# PX4FLOW2_0_CAM_X0.net
KiCad netlist of a schematic drawn in Altium Designer
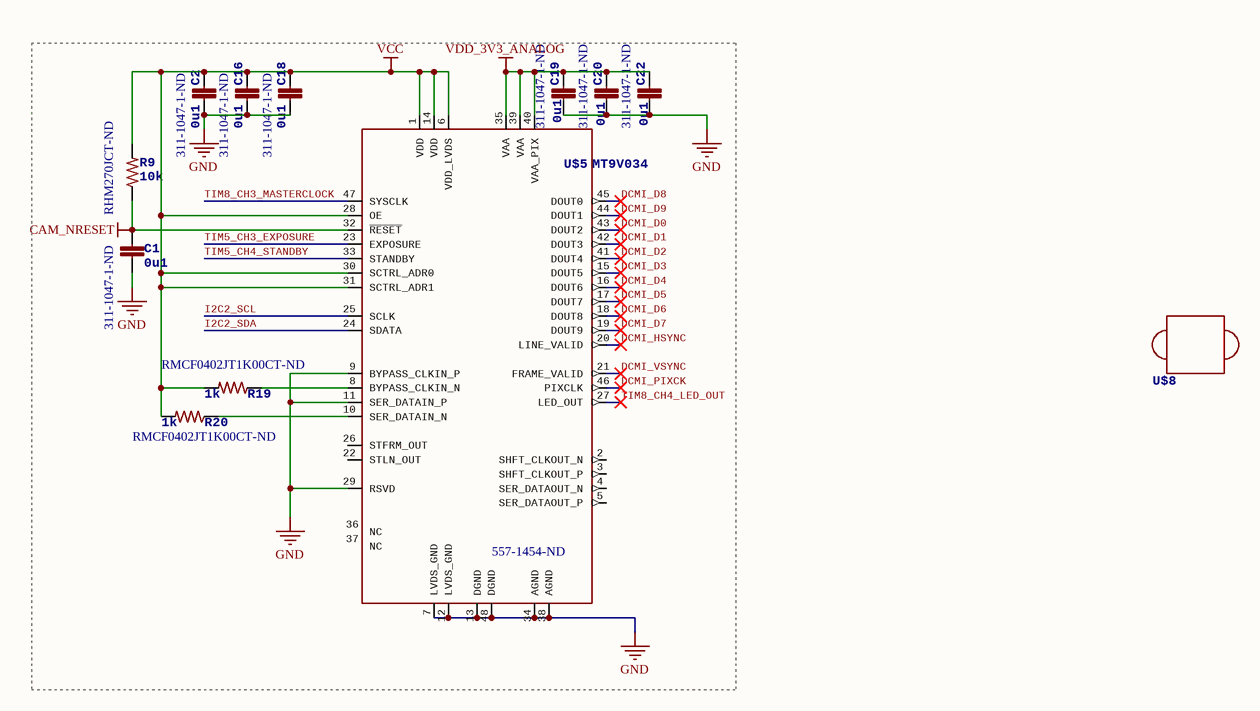
[diagram p0: PX4FLOW2.0_CAM_X0.SchDoc]

(export (version "E")
  (design (tool "Eeschema 10.0.6"))
  (components
    (comp (ref "C1")
      (value "0u1")
      (footprint "0402-CAP")
      (description "CapacitorStandard 0603 ceramic capacitor, and 0.1\" leaded capacitor.")
      (fields
        (field (name "PARTNO") "CC0402ZRY5V7BB104")
        (field (name "SUPPLIER PART NUMBER 1") "311-1047-1-ND")
      )
      (libsource (lib "pixhawk2") (part "CAP0402-CAP"))
    )
    (comp (ref "C2")
      (value "0u1")
      (footprint "0402-CAP")
      (description "CapacitorStandard 0603 ceramic capacitor, and 0.1\" leaded capacitor.")
      (fields
        (field (name "PARTNO") "CC0402ZRY5V7BB104")
        (field (name "SUPPLIER PART NUMBER 1") "311-1047-1-ND")
      )
      (libsource (lib "pixhawk2") (part "CAP0402-CAP"))
    )
    (comp (ref "C16")
      (value "0u1")
      (footprint "0402-CAP")
      (description "CapacitorStandard 0603 ceramic capacitor, and 0.1\" leaded capacitor.")
      (fields
        (field (name "PARTNO") "CC0402ZRY5V7BB104")
        (field (name "SUPPLIER PART NUMBER 1") "311-1047-1-ND")
      )
      (libsource (lib "pixhawk2") (part "CAP0402-CAP"))
    )
    (comp (ref "C18")
      (value "0u1")
      (footprint "0402-CAP")
      (description "CapacitorStandard 0603 ceramic capacitor, and 0.1\" leaded capacitor.")
      (fields
        (field (name "PARTNO") "CC0402ZRY5V7BB104")
        (field (name "SUPPLIER PART NUMBER 1") "311-1047-1-ND")
      )
      (libsource (lib "pixhawk2") (part "CAP0402-CAP"))
    )
    (comp (ref "C19")
      (value "0u1")
      (footprint "0402-CAP")
      (description "CapacitorStandard 0603 ceramic capacitor, and 0.1\" leaded capacitor.")
      (fields
        (field (name "PARTNO") "CC0402ZRY5V7BB104")
        (field (name "SUPPLIER PART NUMBER 1") "311-1047-1-ND")
      )
      (libsource (lib "pixhawk2") (part "CAP0402-CAP"))
    )
    (comp (ref "C20")
      (value "0u1")
      (footprint "0402-CAP")
      (description "CapacitorStandard 0603 ceramic capacitor, and 0.1\" leaded capacitor.")
      (fields
        (field (name "PARTNO") "CC0402ZRY5V7BB104")
        (field (name "SUPPLIER PART NUMBER 1") "311-1047-1-ND")
      )
      (libsource (lib "pixhawk2") (part "CAP0402-CAP"))
    )
    (comp (ref "C22")
      (value "0u1")
      (footprint "0402-CAP")
      (description "CapacitorStandard 0603 ceramic capacitor, and 0.1\" leaded capacitor.")
      (fields
        (field (name "PARTNO") "CC0402ZRY5V7BB104")
        (field (name "SUPPLIER PART NUMBER 1") "311-1047-1-ND")
      )
      (libsource (lib "pixhawk2") (part "CAP0402-CAP"))
    )
    (comp (ref "R9")
      (value "10k")
      (footprint "R0402")
      (fields (field (name "PARTNO") "MCR01MZPJ271") (field (name "SUPPLIER PART NUMBER 1") "RHM270JCT-ND"))
      (libsource (lib "pixhawk2") (part "RESISTOR0402-RES"))
    )
    (comp (ref "R19")
      (value "1k")
      (footprint "R0402")
      (fields
        (field (name "PARTNO") "RMCF0402JT1K00")
        (field (name "SUPPLIER PART NUMBER 1") "RMCF0402JT1K00CT-ND")
      )
      (libsource (lib "pixhawk2") (part "RESISTOR0402-RES"))
    )
    (comp (ref "R20")
      (value "1k")
      (footprint "R0402")
      (fields
        (field (name "PARTNO") "RMCF0402JT1K00")
        (field (name "SUPPLIER PART NUMBER 1") "RMCF0402JT1K00CT-ND")
      )
      (libsource (lib "pixhawk2") (part "RESISTOR0402-RES"))
    )
    (comp (ref "U$5")
      (value "MT9V034")
      (footprint "CLCC-48")
      (fields (field (name "PARTNO") "MT9V034C12STM") (field (name "SUPPLIER PART NUMBER 1") "557-1454-ND"))
      (libsource (lib "3DR") (part "MT9V034"))
    )
    (comp (ref "U$8")
      (value "LENSMOUNT_M12")
      (footprint "LENSMOUNT_LARGE_M12")
      (description "Point Grey compatible M12 lens mount")
      (libsource (lib "3DR") (part "LENSMOUNT_M12"))
    )
  )
  (nets
    (net (code "1") (name "/DCMI_D0") (class "Default")
      (node (ref "U$5") (pin "43") (pinfunction "DOUT2_43") (pintype "output+no_connect"))
    )
    (net (code "2") (name "/DCMI_D1") (class "Default")
      (node (ref "U$5") (pin "42") (pinfunction "DOUT3_42") (pintype "output+no_connect"))
    )
    (net (code "3") (name "/DCMI_D2") (class "Default")
      (node (ref "U$5") (pin "41") (pinfunction "DOUT4_41") (pintype "output+no_connect"))
    )
    (net (code "4") (name "/DCMI_D3") (class "Default")
      (node (ref "U$5") (pin "15") (pinfunction "DOUT5_15") (pintype "output+no_connect"))
    )
    (net (code "5") (name "/DCMI_D4") (class "Default")
      (node (ref "U$5") (pin "16") (pinfunction "DOUT6_16") (pintype "output+no_connect"))
    )
    (net (code "6") (name "/DCMI_D5") (class "Default")
      (node (ref "U$5") (pin "17") (pinfunction "DOUT7_17") (pintype "output+no_connect"))
    )
    (net (code "7") (name "/DCMI_D6") (class "Default")
      (node (ref "U$5") (pin "18") (pinfunction "DOUT8_18") (pintype "output+no_connect"))
    )
    (net (code "8") (name "/DCMI_D7") (class "Default")
      (node (ref "U$5") (pin "19") (pinfunction "DOUT9_19") (pintype "output+no_connect"))
    )
    (net (code "9") (name "/DCMI_D8") (class "Default")
      (node (ref "U$5") (pin "45") (pinfunction "DOUT0_45") (pintype "output+no_connect"))
    )
    (net (code "10") (name "/DCMI_D9") (class "Default")
      (node (ref "U$5") (pin "44") (pinfunction "DOUT1_44") (pintype "output+no_connect"))
    )
    (net (code "11") (name "/DCMI_HSYNC") (class "Default")
      (node (ref "U$5") (pin "20") (pinfunction "LINE_VALID_20") (pintype "output+no_connect"))
    )
    (net (code "12") (name "/DCMI_PIXCK") (class "Default")
      (node (ref "U$5") (pin "46") (pinfunction "PIXCLK_46") (pintype "output+no_connect"))
    )
    (net (code "13") (name "/DCMI_VSYNC") (class "Default")
      (node (ref "U$5") (pin "21") (pinfunction "FRAME_VALID_21") (pintype "output+no_connect"))
    )
    (net (code "14") (name "/I2C2_SCL") (class "Default")
      (node (ref "U$5") (pin "25") (pinfunction "SCLK_25") (pintype "passive"))
    )
    (net (code "15") (name "/I2C2_SDA") (class "Default")
      (node (ref "U$5") (pin "24") (pinfunction "SDATA_24") (pintype "passive"))
    )
    (net (code "16") (name "/TIM5_CH3_EXPOSURE") (class "Default")
      (node (ref "U$5") (pin "23") (pinfunction "EXPOSURE_23") (pintype "passive"))
    )
    (net (code "17") (name "/TIM5_CH4_STANDBY") (class "Default")
      (node (ref "U$5") (pin "33") (pinfunction "STANDBY_33") (pintype "passive"))
    )
    (net (code "18") (name "/TIM8_CH3_MASTERCLOCK") (class "Default")
      (node (ref "U$5") (pin "47") (pinfunction "SYSCLK_47") (pintype "passive"))
    )
    (net (code "19") (name "/TIM8_CH4_LED_OUT") (class "Default")
      (node (ref "U$5") (pin "27") (pinfunction "LED_OUT_27") (pintype "output+no_connect"))
    )
    (net (code "20") (name "CAM_NRESET") (class "Default")
      (node (ref "C1") (pin "1") (pinfunction "1_1") (pintype "passive"))
      (node (ref "R9") (pin "1") (pinfunction "1_1") (pintype "passive"))
      (node (ref "U$5") (pin "32") (pinfunction "~{RESET}_32") (pintype "passive"))
    )
    (net (code "21") (name "GND") (class "Default")
      (node (ref "C1") (pin "2") (pinfunction "2_2") (pintype "passive"))
      (node (ref "C16") (pin "2") (pinfunction "2_2") (pintype "passive"))
      (node (ref "C18") (pin "2") (pinfunction "2_2") (pintype "passive"))
      (node (ref "C19") (pin "2") (pinfunction "2_2") (pintype "passive"))
      (node (ref "C2") (pin "2") (pinfunction "2_2") (pintype "passive"))
      (node (ref "C20") (pin "2") (pinfunction "2_2") (pintype "passive"))
      (node (ref "C22") (pin "2") (pinfunction "2_2") (pintype "passive"))
      (node (ref "U$5") (pin "11") (pinfunction "SER_DATAIN_P_11") (pintype "passive"))
      (node (ref "U$5") (pin "12") (pinfunction "LVDS_GND_12") (pintype "power_in"))
      (node (ref "U$5") (pin "13") (pinfunction "DGND_13") (pintype "power_in"))
      (node (ref "U$5") (pin "29") (pinfunction "RSVD_29") (pintype "passive"))
      (node (ref "U$5") (pin "34") (pinfunction "AGND_34") (pintype "power_in"))
      (node (ref "U$5") (pin "38") (pinfunction "AGND_38") (pintype "power_in"))
      (node (ref "U$5") (pin "48") (pinfunction "DGND_48") (pintype "power_in"))
      (node (ref "U$5") (pin "7") (pinfunction "LVDS_GND_7") (pintype "power_in"))
      (node (ref "U$5") (pin "9") (pinfunction "BYPASS_CLKIN_P_9") (pintype "passive"))
    )
    (net (code "22") (name "Net-(U$5-BYPASS_CLKIN_N)") (class "Default")
      (node (ref "R19") (pin "1") (pinfunction "1_1") (pintype "passive"))
      (node (ref "U$5") (pin "8") (pinfunction "BYPASS_CLKIN_N_8") (pintype "passive"))
    )
    (net (code "23") (name "Net-(U$5-SER_DATAIN_N)") (class "Default")
      (node (ref "R20") (pin "1") (pinfunction "1_1") (pintype "passive"))
      (node (ref "U$5") (pin "10") (pinfunction "SER_DATAIN_N_10") (pintype "passive"))
    )
    (net (code "24") (name "VCC") (class "Default")
      (node (ref "C16") (pin "1") (pinfunction "1_1") (pintype "passive"))
      (node (ref "C18") (pin "1") (pinfunction "1_1") (pintype "passive"))
      (node (ref "C2") (pin "1") (pinfunction "1_1") (pintype "passive"))
      (node (ref "R19") (pin "2") (pinfunction "2_2") (pintype "passive"))
      (node (ref "R20") (pin "2") (pinfunction "2_2") (pintype "passive"))
      (node (ref "R9") (pin "2") (pinfunction "2_2") (pintype "passive"))
      (node (ref "U$5") (pin "1") (pinfunction "VDD_1") (pintype "passive"))
      (node (ref "U$5") (pin "14") (pinfunction "VDD_14") (pintype "passive"))
      (node (ref "U$5") (pin "28") (pinfunction "OE_28") (pintype "passive"))
      (node (ref "U$5") (pin "30") (pinfunction "SCTRL_ADR0_30") (pintype "passive"))
      (node (ref "U$5") (pin "31") (pinfunction "SCTRL_ADR1_31") (pintype "passive"))
      (node (ref "U$5") (pin "6") (pinfunction "VDD_LVDS_6") (pintype "passive"))
    )
    (net (code "25") (name "VDD_3V3_ANALOG") (class "Default")
      (node (ref "C19") (pin "1") (pinfunction "1_1") (pintype "passive"))
      (node (ref "C20") (pin "1") (pinfunction "1_1") (pintype "passive"))
      (node (ref "C22") (pin "1") (pinfunction "1_1") (pintype "passive"))
      (node (ref "U$5") (pin "35") (pinfunction "VAA_35") (pintype "passive"))
      (node (ref "U$5") (pin "39") (pinfunction "VAA_39") (pintype "passive"))
      (node (ref "U$5") (pin "40") (pinfunction "VAA_PIX_40") (pintype "passive"))
    )
    (net (code "26") (name "unconnected-(U$5-NC-Pad36)") (class "Default")
      (node (ref "U$5") (pin "36") (pinfunction "NC_36") (pintype "passive"))
    )
    (net (code "27") (name "unconnected-(U$5-NC-Pad37)") (class "Default")
      (node (ref "U$5") (pin "37") (pinfunction "NC_37") (pintype "passive"))
    )
    (net (code "28") (name "unconnected-(U$5-SER_DATAOUT_N-Pad4)") (class "Default")
      (node (ref "U$5") (pin "4") (pinfunction "SER_DATAOUT_N_4") (pintype "output"))
    )
    (net (code "29") (name "unconnected-(U$5-SER_DATAOUT_P-Pad5)") (class "Default")
      (node (ref "U$5") (pin "5") (pinfunction "SER_DATAOUT_P_5") (pintype "output"))
    )
    (net (code "30") (name "unconnected-(U$5-SHFT_CLKOUT_N-Pad2)") (class "Default")
      (node (ref "U$5") (pin "2") (pinfunction "SHFT_CLKOUT_N_2") (pintype "output"))
    )
    (net (code "31") (name "unconnected-(U$5-SHFT_CLKOUT_P-Pad3)") (class "Default")
      (node (ref "U$5") (pin "3") (pinfunction "SHFT_CLKOUT_P_3") (pintype "output"))
    )
    (net (code "32") (name "unconnected-(U$5-STFRM_OUT-Pad26)") (class "Default")
      (node (ref "U$5") (pin "26") (pinfunction "STFRM_OUT_26") (pintype "passive"))
    )
    (net (code "33") (name "unconnected-(U$5-STLN_OUT-Pad22)") (class "Default")
      (node (ref "U$5") (pin "22") (pinfunction "STLN_OUT_22") (pintype "passive"))
    )
  )
)
